# 1_P1.net
KiCad netlist of a schematic drawn in Altium Designer
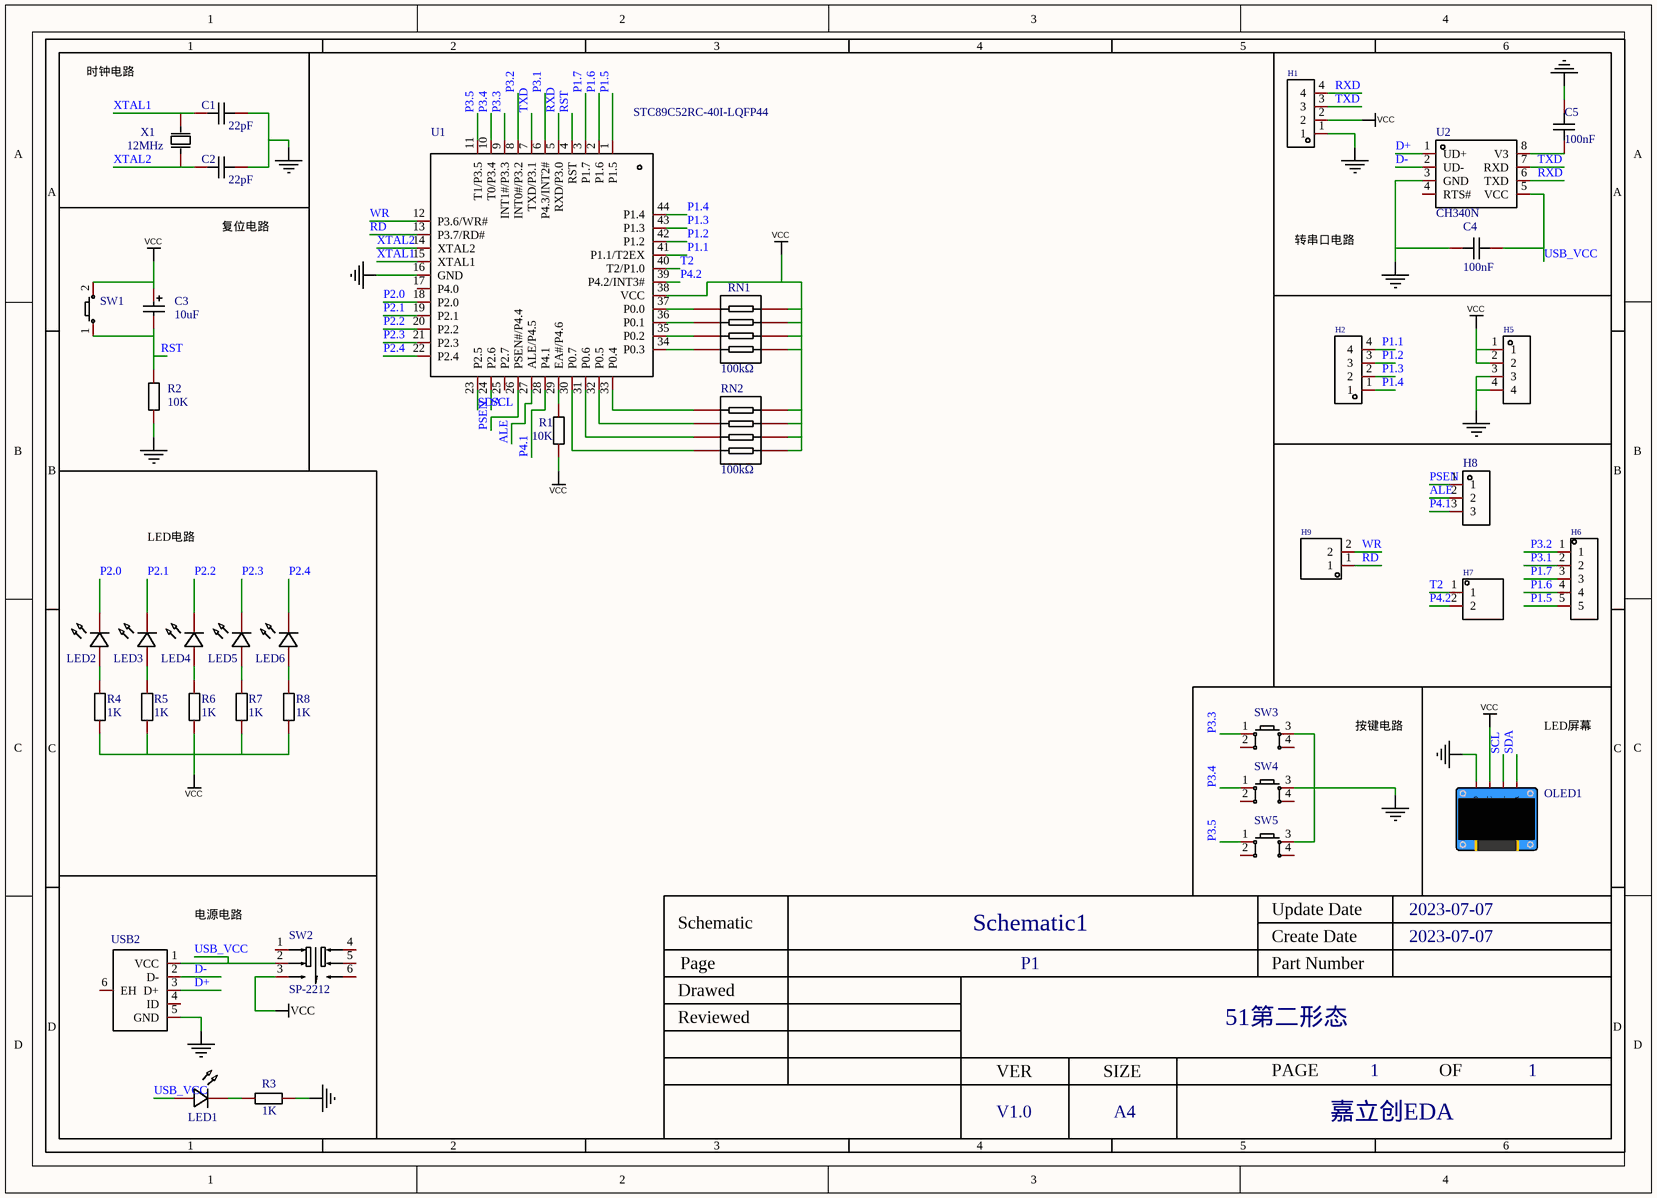
[diagram p0: 1_P1.schdoc]

(export (version "E")
  (design (tool "Eeschema 10.0.6"))
  (components
    (comp (ref "C1")
      (value "22pF")
      (description "容值:100nF;精度:±10%;额定电压:50V;材质(温度系数):X7R;")
      (fields
        (field (name "NAME") "22pF")
        (field (name "MANUFACTURER") "YAGEO(国巨)")
        (field (name "MANUFACTURER PART") "CC0603KRX7R9BB104")
      )
      (libsource (lib "altium-import") (part "root_0_CC0603KRX7R9BB104_"))
    )
    (comp (ref "C2")
      (value "22pF")
      (description "容值:100nF;精度:±10%;额定电压:50V;材质(温度系数):X7R;")
      (fields
        (field (name "NAME") "22pF")
        (field (name "MANUFACTURER") "YAGEO(国巨)")
        (field (name "MANUFACTURER PART") "CC0603KRX7R9BB104")
      )
      (libsource (lib "altium-import") (part "root_0_CC0603KRX7R9BB104_"))
    )
    (comp (ref "C3")
      (value "10uF")
      (fields (field (name "NAME") "10uF"))
      (libsource (lib "altium-import") (part "root_1_C_Ele_SMD_3x5.4mm_"))
    )
    (comp (ref "C4")
      (value "100nF")
      (fields (field (name "NAME") "100nF"))
      (libsource (lib "altium-import") (part "root_0_CAP_0603_"))
    )
    (comp (ref "C5")
      (value "100nF")
      (fields (field (name "NAME") "100nF"))
      (libsource (lib "altium-import") (part "root_1_CAP_0603_"))
    )
    (comp (ref "H1")
      (value "HDR-M_2.54_1x4P")
      (fields (field (name "MANUFACTURER") "XFCN(兴飞)") (field (name "MANUFACTURER PART") "PZ254V-11-04P"))
      (libsource (lib "altium-import") (part "root_2_HDR-M_2.54_1x4P_"))
    )
    (comp (ref "H2")
      (value "HDR-M_2.54_1x4P")
      (fields (field (name "MANUFACTURER") "XFCN(兴飞)") (field (name "MANUFACTURER PART") "PZ254V-11-04P"))
      (libsource (lib "altium-import") (part "root_2_HDR-M_2.54_1x4P_"))
    )
    (comp (ref "H5")
      (value "HDR-M_2.54_1x4P")
      (fields (field (name "MANUFACTURER") "XFCN(兴飞)") (field (name "MANUFACTURER PART") "PZ254V-11-04P"))
      (libsource (lib "altium-import") (part "root_0_HDR-M_2.54_1x4P_"))
    )
    (comp (ref "H6")
      (value "HDR-M_2.54_1x5P")
      (fields (field (name "MANUFACTURER") "MINTRON(明硕)") (field (name "MANUFACTURER PART") "MTP125-1105S1"))
      (libsource (lib "altium-import") (part "root_0_HDR-M_2.54_1x5P_"))
    )
    (comp (ref "H7")
      (value "HDR-M_2.54_1x2P")
      (fields (field (name "MANUFACTURER") "Ckmtw(灿科盟)") (field (name "MANUFACTURER PART") "B-2100S02P-A110"))
      (libsource (lib "altium-import") (part "root_0_HDR-M_2.54_1x2P_"))
    )
    (comp (ref "H8")
      (value "HDR-M_2.54_1x3P")
      (libsource (lib "altium-import") (part "root_0_HDR-M_2.54_1x3P_"))
    )
    (comp (ref "H9")
      (value "HDR-M_2.54_1x2P")
      (fields (field (name "MANUFACTURER") "Ckmtw(灿科盟)") (field (name "MANUFACTURER PART") "B-2100S02P-A110"))
      (libsource (lib "altium-import") (part "root_2_HDR-M_2.54_1x2P_"))
    )
    (comp (ref "LED1") (value "LED_TH-R_3mm") (libsource (lib "altium-import") (part "root_0_LED_TH-R_3mm_")))
    (comp (ref "LED2") (value "LED_TH-R_3mm") (libsource (lib "altium-import") (part "root_1_LED_TH-R_3mm_")))
    (comp (ref "LED3") (value "LED_TH-R_3mm") (libsource (lib "altium-import") (part "root_1_LED_TH-R_3mm_")))
    (comp (ref "LED4") (value "LED_TH-R_3mm") (libsource (lib "altium-import") (part "root_1_LED_TH-R_3mm_")))
    (comp (ref "LED5") (value "LED_TH-R_3mm") (libsource (lib "altium-import") (part "root_1_LED_TH-R_3mm_")))
    (comp (ref "LED6") (value "LED_TH-R_3mm") (libsource (lib "altium-import") (part "root_1_LED_TH-R_3mm_")))
    (comp (ref "OLED1")
      (value "0.96OLED模块_4P")
      (libsource (lib "altium-import") (part "root_0_0.96OLED模块_4P_"))
    )
    (comp (ref "R1")
      (value "10K")
      (fields (field (name "NAME") "10K"))
      (libsource (lib "altium-import") (part "root_1_Res_0603_"))
    )
    (comp (ref "R2")
      (value "10K")
      (fields (field (name "NAME") "10K"))
      (libsource (lib "altium-import") (part "root_1_Res_0603_"))
    )
    (comp (ref "R3")
      (value "1K")
      (fields (field (name "NAME") "1K"))
      (libsource (lib "altium-import") (part "root_0_Res_0603_"))
    )
    (comp (ref "R4")
      (value "1K")
      (fields (field (name "NAME") "1K"))
      (libsource (lib "altium-import") (part "root_1_Res_0603_"))
    )
    (comp (ref "R5")
      (value "1K")
      (fields (field (name "NAME") "1K"))
      (libsource (lib "altium-import") (part "root_1_Res_0603_"))
    )
    (comp (ref "R6")
      (value "1K")
      (fields (field (name "NAME") "1K"))
      (libsource (lib "altium-import") (part "root_1_Res_0603_"))
    )
    (comp (ref "R7")
      (value "1K")
      (fields (field (name "NAME") "1K"))
      (libsource (lib "altium-import") (part "root_1_Res_0603_"))
    )
    (comp (ref "R8")
      (value "1K")
      (fields (field (name "NAME") "1K"))
      (libsource (lib "altium-import") (part "root_1_Res_0603_"))
    )
    (comp (ref "RN1")
      (value "100kΩ")
      (description "阻值:10kΩ;精度:±5%;单个元件功率:62.5mW;电阻器数:4;")
      (fields
        (field (name "NAME") "100kΩ")
        (field (name "MANUFACTURER") "UNI-ROYAL(厚声)")
        (field (name "MANUFACTURER PART") "4D03WGJ0103T5E")
      )
      (libsource (lib "altium-import") (part "root_0_4D03WGJ0103T5E_"))
    )
    (comp (ref "RN2")
      (value "100kΩ")
      (description "阻值:10kΩ;精度:±5%;单个元件功率:62.5mW;电阻器数:4;")
      (fields
        (field (name "NAME") "100kΩ")
        (field (name "MANUFACTURER") "UNI-ROYAL(厚声)")
        (field (name "MANUFACTURER PART") "4D03WGJ0103T5E")
      )
      (libsource (lib "altium-import") (part "root_2_4D03WGJ0103T5E_"))
    )
    (comp (ref "SW1")
      (value "Key_SMD_3x4x2")
      (libsource (lib "altium-import") (part "root_1_Key_SMD_3x4x2_"))
    )
    (comp (ref "SW2")
      (value "SP-2212")
      (fields (field (name "NAME") "SP-2212") (field (name "MANUFACTURER") "RISHENG(日昇)"))
      (libsource (lib "altium-import") (part "root_3_SP-2212_"))
    )
    (comp (ref "SW3")
      (value "Key_SMD_12x12x7.3")
      (libsource (lib "altium-import") (part "root_0_Key_SMD_12x12x7.3_"))
    )
    (comp (ref "SW4")
      (value "Key_SMD_12x12x7.3")
      (libsource (lib "altium-import") (part "root_0_Key_SMD_12x12x7.3_"))
    )
    (comp (ref "SW5")
      (value "Key_SMD_12x12x7.3")
      (libsource (lib "altium-import") (part "root_0_Key_SMD_12x12x7.3_"))
    )
    (comp (ref "U1")
      (value "STC89C52RC-40I-LQFP44")
      (description "CPU内核:51系列;CPU最大主频:-;程序存储容量:8KB;程序存储器类型:FLASH;RAM总容量:512Byte;GPIO端口数量:39;")
      (fields (field (name "NAME") "STC89C52RC-40I-LQFP44") (field (name "MANUFACTURER") "STC(宏晶)"))
      (libsource (lib "altium-import") (part "root_3_STC89C52RC-40I-LQFP44_"))
    )
    (comp (ref "U2")
      (value "CH340N")
      (fields (field (name "NAME") "CH340N") (field (name "MANUFACTURER") "WCH(南京沁恒)"))
      (libsource (lib "altium-import") (part "root_0_CH340N_"))
    )
    (comp (ref "USB2") (value "USB_Micro-B") (libsource (lib "altium-import") (part "root_0_USB_Micro-B_")))
    (comp (ref "X1")
      (value "12MHz")
      (description "频率:12MHz;频率公差:±20ppm;负载电容:20pF;")
      (fields
        (field (name "NAME") "12MHz")
        (field (name "MANUFACTURER") "YXC(扬兴晶振)")
        (field (name "MANUFACTURER PART") "X49SD12MSD2SC")
      )
      (libsource (lib "altium-import") (part "root_1_X49SD12MSD2SC_"))
    )
  )
  (nets
    (net (code "1") (name "/ALE") (class "Default")
      (node (ref "H8") (pin "2") (pinfunction "2_2") (pintype "passive"))
      (node (ref "U1") (pin "27") (pinfunction "ALE/P4.5_27") (pintype "passive"))
    )
    (net (code "2") (name "/D+") (class "Default")
      (node (ref "U2") (pin "1") (pinfunction "UD+_1") (pintype "passive"))
      (node (ref "USB2") (pin "3") (pinfunction "D+_3") (pintype "passive"))
    )
    (net (code "3") (name "/D-") (class "Default")
      (node (ref "U2") (pin "2") (pinfunction "UD-_2") (pintype "passive"))
      (node (ref "USB2") (pin "2") (pinfunction "D-_2") (pintype "passive"))
    )
    (net (code "4") (name "/P1.1") (class "Default")
      (node (ref "H2") (pin "4") (pinfunction "4_4") (pintype "passive"))
      (node (ref "U1") (pin "41") (pinfunction "P1.1/T2EX_41") (pintype "passive"))
    )
    (net (code "5") (name "/P1.2") (class "Default")
      (node (ref "H2") (pin "3") (pinfunction "3_3") (pintype "passive"))
      (node (ref "U1") (pin "42") (pinfunction "P1.2_42") (pintype "passive"))
    )
    (net (code "6") (name "/P1.3") (class "Default")
      (node (ref "H2") (pin "2") (pinfunction "2_2") (pintype "passive"))
      (node (ref "U1") (pin "43") (pinfunction "P1.3_43") (pintype "passive"))
    )
    (net (code "7") (name "/P1.4") (class "Default")
      (node (ref "H2") (pin "1") (pinfunction "1_1") (pintype "passive"))
      (node (ref "U1") (pin "44") (pinfunction "P1.4_44") (pintype "passive"))
    )
    (net (code "8") (name "/P1.5") (class "Default")
      (node (ref "H6") (pin "5") (pinfunction "5_5") (pintype "passive"))
      (node (ref "U1") (pin "1") (pinfunction "P1.5_1") (pintype "passive"))
    )
    (net (code "9") (name "/P1.6") (class "Default")
      (node (ref "H6") (pin "4") (pinfunction "4_4") (pintype "passive"))
      (node (ref "U1") (pin "2") (pinfunction "P1.6_2") (pintype "passive"))
    )
    (net (code "10") (name "/P1.7") (class "Default")
      (node (ref "H6") (pin "3") (pinfunction "3_3") (pintype "passive"))
      (node (ref "U1") (pin "3") (pinfunction "P1.7_3") (pintype "passive"))
    )
    (net (code "11") (name "/P2.0") (class "Default")
      (node (ref "LED2") (pin "2") (pinfunction "A_2") (pintype "passive"))
      (node (ref "U1") (pin "18") (pinfunction "P2.0_18") (pintype "passive"))
    )
    (net (code "12") (name "/P2.1") (class "Default")
      (node (ref "LED3") (pin "2") (pinfunction "A_2") (pintype "passive"))
      (node (ref "U1") (pin "19") (pinfunction "P2.1_19") (pintype "passive"))
    )
    (net (code "13") (name "/P2.2") (class "Default")
      (node (ref "LED4") (pin "2") (pinfunction "A_2") (pintype "passive"))
      (node (ref "U1") (pin "20") (pinfunction "P2.2_20") (pintype "passive"))
    )
    (net (code "14") (name "/P2.3") (class "Default")
      (node (ref "LED5") (pin "2") (pinfunction "A_2") (pintype "passive"))
      (node (ref "U1") (pin "21") (pinfunction "P2.3_21") (pintype "passive"))
    )
    (net (code "15") (name "/P2.4") (class "Default")
      (node (ref "LED6") (pin "2") (pinfunction "A_2") (pintype "passive"))
      (node (ref "U1") (pin "22") (pinfunction "P2.4_22") (pintype "passive"))
    )
    (net (code "16") (name "/P3.1") (class "Default")
      (node (ref "H6") (pin "2") (pinfunction "2_2") (pintype "passive"))
      (node (ref "U1") (pin "6") (pinfunction "P4.3/INT2#_6") (pintype "passive"))
    )
    (net (code "17") (name "/P3.2") (class "Default")
      (node (ref "H6") (pin "1") (pinfunction "1_1") (pintype "passive"))
      (node (ref "U1") (pin "8") (pinfunction "INT0#/P3.2_8") (pintype "passive"))
    )
    (net (code "18") (name "/P3.3") (class "Default")
      (node (ref "SW3") (pin "1") (pinfunction "1_1") (pintype "passive"))
      (node (ref "U1") (pin "9") (pinfunction "INT1#/P3.3_9") (pintype "passive"))
    )
    (net (code "19") (name "/P3.4") (class "Default")
      (node (ref "SW4") (pin "1") (pinfunction "1_1") (pintype "passive"))
      (node (ref "U1") (pin "10") (pinfunction "T0/P3.4_10") (pintype "passive"))
    )
    (net (code "20") (name "/P3.5") (class "Default")
      (node (ref "SW5") (pin "1") (pinfunction "1_1") (pintype "passive"))
      (node (ref "U1") (pin "11") (pinfunction "T1/P3.5_11") (pintype "passive"))
    )
    (net (code "21") (name "/P4.1") (class "Default")
      (node (ref "H8") (pin "3") (pinfunction "3_3") (pintype "passive"))
      (node (ref "U1") (pin "28") (pinfunction "P4.1_28") (pintype "passive"))
    )
    (net (code "22") (name "/P4.2") (class "Default")
      (node (ref "H7") (pin "2") (pinfunction "2_2") (pintype "passive"))
      (node (ref "U1") (pin "39") (pinfunction "P4.2/INT3#_39") (pintype "passive"))
    )
    (net (code "23") (name "/PSEN") (class "Default")
      (node (ref "H8") (pin "1") (pinfunction "1_1") (pintype "passive"))
      (node (ref "U1") (pin "26") (pinfunction "PSEN#/P4.4_26") (pintype "passive"))
    )
    (net (code "24") (name "/RD") (class "Default")
      (node (ref "H9") (pin "1") (pinfunction "1_1") (pintype "passive"))
      (node (ref "U1") (pin "13") (pinfunction "P3.7/RD#_13") (pintype "passive"))
    )
    (net (code "25") (name "/RST") (class "Default")
      (node (ref "C3") (pin "2") (pinfunction "2_2") (pintype "passive"))
      (node (ref "R2") (pin "2") (pinfunction "2_2") (pintype "passive"))
      (node (ref "SW1") (pin "1") (pinfunction "1_1") (pintype "passive"))
      (node (ref "U1") (pin "4") (pinfunction "RST_4") (pintype "passive"))
    )
    (net (code "26") (name "/RXD") (class "Default")
      (node (ref "H1") (pin "4") (pinfunction "4_4") (pintype "passive"))
      (node (ref "U1") (pin "5") (pinfunction "RXD/P3.0_5") (pintype "passive"))
      (node (ref "U2") (pin "6") (pinfunction "TXD_6") (pintype "passive"))
    )
    (net (code "27") (name "/SCL") (class "Default")
      (node (ref "OLED1") (pin "3") (pinfunction "SCL_3") (pintype "passive"))
      (node (ref "U1") (pin "24") (pinfunction "P2.6_24") (pintype "passive"))
    )
    (net (code "28") (name "/SDA") (class "Default")
      (node (ref "OLED1") (pin "4") (pinfunction "SDA_4") (pintype "passive"))
      (node (ref "U1") (pin "23") (pinfunction "P2.5_23") (pintype "passive"))
    )
    (net (code "29") (name "/T2") (class "Default")
      (node (ref "H7") (pin "1") (pinfunction "1_1") (pintype "passive"))
      (node (ref "U1") (pin "40") (pinfunction "T2/P1.0_40") (pintype "passive"))
    )
    (net (code "30") (name "/TXD") (class "Default")
      (node (ref "H1") (pin "3") (pinfunction "3_3") (pintype "passive"))
      (node (ref "U1") (pin "7") (pinfunction "TXD/P3.1_7") (pintype "passive"))
      (node (ref "U2") (pin "7") (pinfunction "RXD_7") (pintype "passive"))
    )
    (net (code "31") (name "/USB_VCC") (class "Default")
      (node (ref "C4") (pin "2") (pinfunction "2_2") (pintype "passive"))
      (node (ref "LED1") (pin "1") (pinfunction "C_1") (pintype "passive"))
      (node (ref "SW2") (pin "2") (pinfunction "2_2") (pintype "passive"))
      (node (ref "U2") (pin "5") (pinfunction "VCC_5") (pintype "passive"))
      (node (ref "USB2") (pin "1") (pinfunction "VCC_1") (pintype "passive"))
    )
    (net (code "32") (name "/WR") (class "Default")
      (node (ref "H9") (pin "2") (pinfunction "2_2") (pintype "passive"))
      (node (ref "U1") (pin "12") (pinfunction "P3.6/WR#_12") (pintype "passive"))
    )
    (net (code "33") (name "/XTAL1") (class "Default")
      (node (ref "C1") (pin "1") (pinfunction "1_1") (pintype "passive"))
      (node (ref "U1") (pin "15") (pinfunction "XTAL1_15") (pintype "passive"))
      (node (ref "X1") (pin "1") (pinfunction "OSC1_1") (pintype "passive"))
    )
    (net (code "34") (name "/XTAL2") (class "Default")
      (node (ref "C2") (pin "1") (pinfunction "1_1") (pintype "passive"))
      (node (ref "U1") (pin "14") (pinfunction "XTAL2_14") (pintype "passive"))
      (node (ref "X1") (pin "2") (pinfunction "OSC2_2") (pintype "passive"))
    )
    (net (code "35") (name "<NO NET>") (class "Default")
      (node (ref "C1") (pin "2") (pinfunction "2_2") (pintype "passive"))
      (node (ref "C2") (pin "2") (pinfunction "2_2") (pintype "passive"))
      (node (ref "C4") (pin "1") (pinfunction "1_1") (pintype "passive"))
      (node (ref "C5") (pin "2") (pinfunction "2_2") (pintype "passive"))
      (node (ref "H1") (pin "1") (pinfunction "1_1") (pintype "passive"))
      (node (ref "H5") (pin "3") (pinfunction "3_3") (pintype "passive"))
      (node (ref "H5") (pin "4") (pinfunction "4_4") (pintype "passive"))
      (node (ref "OLED1") (pin "1") (pinfunction "GND_1") (pintype "passive"))
      (node (ref "R2") (pin "1") (pinfunction "1_1") (pintype "passive"))
      (node (ref "R3") (pin "2") (pinfunction "2_2") (pintype "passive"))
      (node (ref "SW3") (pin "3") (pinfunction "3_3") (pintype "passive"))
      (node (ref "SW4") (pin "3") (pinfunction "3_3") (pintype "passive"))
      (node (ref "SW5") (pin "3") (pinfunction "3_3") (pintype "passive"))
      (node (ref "U1") (pin "16") (pinfunction "GND_16") (pintype "passive"))
      (node (ref "U2") (pin "3") (pinfunction "GND_3") (pintype "passive"))
      (node (ref "USB2") (pin "5") (pinfunction "GND_5") (pintype "passive"))
    )
    (net (code "36") (name "Net-(LED1-A)") (class "Default")
      (node (ref "LED1") (pin "2") (pinfunction "A_2") (pintype "passive"))
      (node (ref "R3") (pin "1") (pinfunction "1_1") (pintype "passive"))
    )
    (net (code "37") (name "Net-(LED2-C)") (class "Default")
      (node (ref "LED2") (pin "1") (pinfunction "C_1") (pintype "passive"))
      (node (ref "R4") (pin "2") (pinfunction "2_2") (pintype "passive"))
    )
    (net (code "38") (name "Net-(LED3-C)") (class "Default")
      (node (ref "LED3") (pin "1") (pinfunction "C_1") (pintype "passive"))
      (node (ref "R5") (pin "2") (pinfunction "2_2") (pintype "passive"))
    )
    (net (code "39") (name "Net-(LED4-C)") (class "Default")
      (node (ref "LED4") (pin "1") (pinfunction "C_1") (pintype "passive"))
      (node (ref "R6") (pin "2") (pinfunction "2_2") (pintype "passive"))
    )
    (net (code "40") (name "Net-(LED5-C)") (class "Default")
      (node (ref "LED5") (pin "1") (pinfunction "C_1") (pintype "passive"))
      (node (ref "R7") (pin "2") (pinfunction "2_2") (pintype "passive"))
    )
    (net (code "41") (name "Net-(LED6-C)") (class "Default")
      (node (ref "LED6") (pin "1") (pinfunction "C_1") (pintype "passive"))
      (node (ref "R8") (pin "2") (pinfunction "2_2") (pintype "passive"))
    )
    (net (code "42") (name "Net-(U1-EA#{slash}P4.6)") (class "Default")
      (node (ref "R1") (pin "2") (pinfunction "2_2") (pintype "passive"))
      (node (ref "U1") (pin "29") (pinfunction "EA#/P4.6_29") (pintype "passive"))
    )
    (net (code "43") (name "Net-(U1-P0.0)") (class "Default")
      (node (ref "RN1") (pin "1") (pinfunction "1_1") (pintype "passive"))
      (node (ref "U1") (pin "37") (pinfunction "P0.0_37") (pintype "passive"))
    )
    (net (code "44") (name "Net-(U1-P0.1)") (class "Default")
      (node (ref "RN1") (pin "2") (pinfunction "2_2") (pintype "passive"))
      (node (ref "U1") (pin "36") (pinfunction "P0.1_36") (pintype "passive"))
    )
    (net (code "45") (name "Net-(U1-P0.2)") (class "Default")
      (node (ref "RN1") (pin "3") (pinfunction "3_3") (pintype "passive"))
      (node (ref "U1") (pin "35") (pinfunction "P0.2_35") (pintype "passive"))
    )
    (net (code "46") (name "Net-(U1-P0.3)") (class "Default")
      (node (ref "RN1") (pin "4") (pinfunction "4_4") (pintype "passive"))
      (node (ref "U1") (pin "34") (pinfunction "P0.3_34") (pintype "passive"))
    )
    (net (code "47") (name "Net-(U1-P0.4)") (class "Default")
      (node (ref "RN2") (pin "5") (pinfunction "5_5") (pintype "passive"))
      (node (ref "U1") (pin "33") (pinfunction "P0.4_33") (pintype "passive"))
    )
    (net (code "48") (name "Net-(U1-P0.5)") (class "Default")
      (node (ref "RN2") (pin "6") (pinfunction "6_6") (pintype "passive"))
      (node (ref "U1") (pin "32") (pinfunction "P0.5_32") (pintype "passive"))
    )
    (net (code "49") (name "Net-(U1-P0.6)") (class "Default")
      (node (ref "RN2") (pin "7") (pinfunction "7_7") (pintype "passive"))
      (node (ref "U1") (pin "31") (pinfunction "P0.6_31") (pintype "passive"))
    )
    (net (code "50") (name "Net-(U1-P0.7)") (class "Default")
      (node (ref "RN2") (pin "8") (pinfunction "8_8") (pintype "passive"))
      (node (ref "U1") (pin "30") (pinfunction "P0.7_30") (pintype "passive"))
    )
    (net (code "51") (name "Net-(U2-V3)") (class "Default")
      (node (ref "C5") (pin "1") (pinfunction "1_1") (pintype "passive"))
      (node (ref "U2") (pin "8") (pinfunction "V3_8") (pintype "passive"))
    )
    (net (code "52") (name "VCC") (class "Default")
      (node (ref "C3") (pin "1") (pinfunction "1_1") (pintype "passive"))
      (node (ref "H1") (pin "2") (pinfunction "2_2") (pintype "passive"))
      (node (ref "H5") (pin "1") (pinfunction "1_1") (pintype "passive"))
      (node (ref "H5") (pin "2") (pinfunction "2_2") (pintype "passive"))
      (node (ref "OLED1") (pin "2") (pinfunction "VCC_2") (pintype "passive"))
      (node (ref "R1") (pin "1") (pinfunction "1_1") (pintype "passive"))
      (node (ref "R4") (pin "1") (pinfunction "1_1") (pintype "passive"))
      (node (ref "R5") (pin "1") (pinfunction "1_1") (pintype "passive"))
      (node (ref "R6") (pin "1") (pinfunction "1_1") (pintype "passive"))
      (node (ref "R7") (pin "1") (pinfunction "1_1") (pintype "passive"))
      (node (ref "R8") (pin "1") (pinfunction "1_1") (pintype "passive"))
      (node (ref "RN1") (pin "5") (pinfunction "5_5") (pintype "passive"))
      (node (ref "RN1") (pin "6") (pinfunction "6_6") (pintype "passive"))
      (node (ref "RN1") (pin "7") (pinfunction "7_7") (pintype "passive"))
      (node (ref "RN1") (pin "8") (pinfunction "8_8") (pintype "passive"))
      (node (ref "RN2") (pin "1") (pinfunction "1_1") (pintype "passive"))
      (node (ref "RN2") (pin "2") (pinfunction "2_2") (pintype "passive"))
      (node (ref "RN2") (pin "3") (pinfunction "3_3") (pintype "passive"))
      (node (ref "RN2") (pin "4") (pinfunction "4_4") (pintype "passive"))
      (node (ref "SW1") (pin "2") (pinfunction "2_2") (pintype "passive"))
      (node (ref "SW2") (pin "3") (pinfunction "3_3") (pintype "passive"))
      (node (ref "U1") (pin "38") (pinfunction "VCC_38") (pintype "passive"))
    )
    (net (code "53") (name "unconnected-(SW2-Pad1)") (class "Default")
      (node (ref "SW2") (pin "1") (pinfunction "1_1") (pintype "passive"))
    )
    (net (code "54") (name "unconnected-(SW2-Pad4)") (class "Default")
      (node (ref "SW2") (pin "4") (pinfunction "4_4") (pintype "passive"))
    )
    (net (code "55") (name "unconnected-(SW2-Pad5)") (class "Default")
      (node (ref "SW2") (pin "5") (pinfunction "5_5") (pintype "passive"))
    )
    (net (code "56") (name "unconnected-(SW2-Pad6)") (class "Default")
      (node (ref "SW2") (pin "6") (pinfunction "6_6") (pintype "passive"))
    )
    (net (code "57") (name "unconnected-(SW3-Pad2)") (class "Default")
      (node (ref "SW3") (pin "2") (pinfunction "2_2") (pintype "passive"))
    )
    (net (code "58") (name "unconnected-(SW3-Pad4)") (class "Default")
      (node (ref "SW3") (pin "4") (pinfunction "4_4") (pintype "passive"))
    )
    (net (code "59") (name "unconnected-(SW4-Pad2)") (class "Default")
      (node (ref "SW4") (pin "2") (pinfunction "2_2") (pintype "passive"))
    )
    (net (code "60") (name "unconnected-(SW4-Pad4)") (class "Default")
      (node (ref "SW4") (pin "4") (pinfunction "4_4") (pintype "passive"))
    )
    (net (code "61") (name "unconnected-(SW5-Pad2)") (class "Default")
      (node (ref "SW5") (pin "2") (pinfunction "2_2") (pintype "passive"))
    )
    (net (code "62") (name "unconnected-(SW5-Pad4)") (class "Default")
      (node (ref "SW5") (pin "4") (pinfunction "4_4") (pintype "passive"))
    )
    (net (code "63") (name "unconnected-(U1-P2.7-Pad25)") (class "Default")
      (node (ref "U1") (pin "25") (pinfunction "P2.7_25") (pintype "passive"))
    )
    (net (code "64") (name "unconnected-(U1-P4.0-Pad17)") (class "Default")
      (node (ref "U1") (pin "17") (pinfunction "P4.0_17") (pintype "passive"))
    )
    (net (code "65") (name "unconnected-(U2-RTS#-Pad4)") (class "Default")
      (node (ref "U2") (pin "4") (pinfunction "RTS#_4") (pintype "passive"))
    )
    (net (code "66") (name "unconnected-(USB2-EH-Pad6)") (class "Default")
      (node (ref "USB2") (pin "6") (pinfunction "EH_6") (pintype "passive"))
    )
    (net (code "67") (name "unconnected-(USB2-ID-Pad4)") (class "Default")
      (node (ref "USB2") (pin "4") (pinfunction "ID_4") (pintype "passive"))
    )
  )
)
